# TH4.net
KiCad netlist of a schematic drawn in Altium Designer
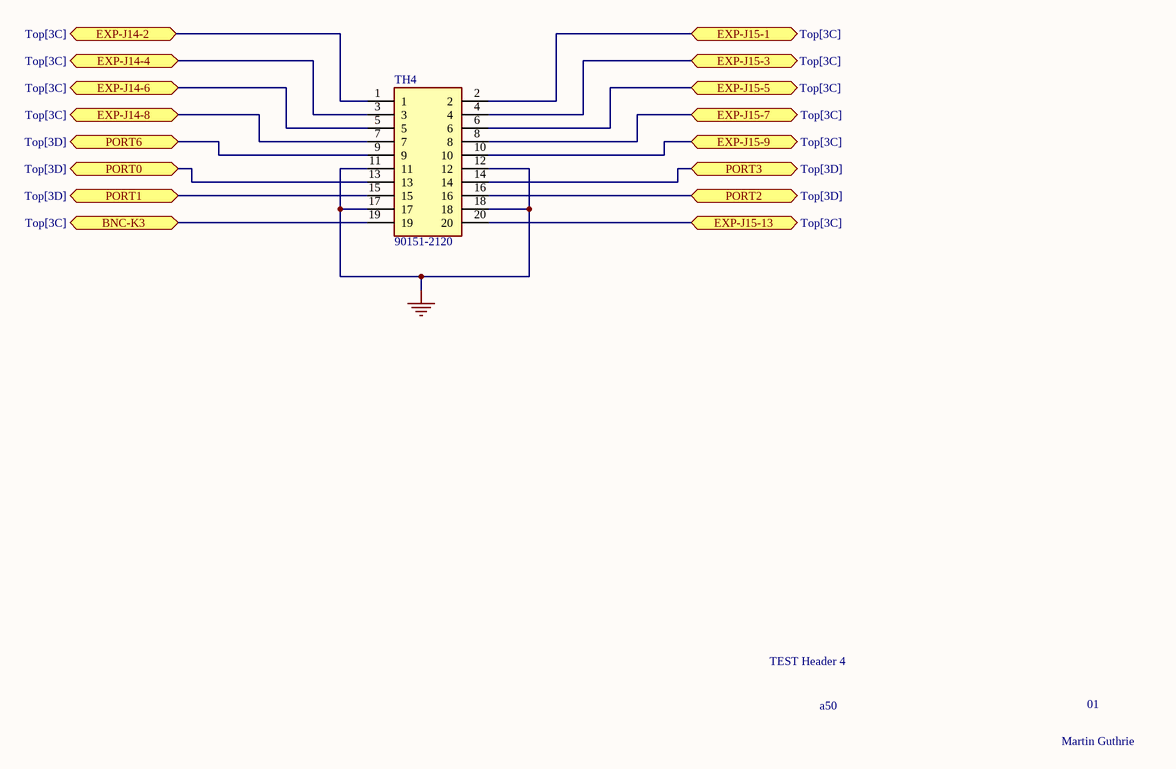
[diagram p0: TH4.SchDoc]

(export (version "E")
  (design (tool "Eeschema 10.0.6"))
  (components
    (comp (ref "TH4")
      (value "90151-2120")
      (footprint "PcbLib:90151-2120")
      (description "Connector")
      (fields (field (name "MOUSER PART NUMBER") "538-90151-2120"))
      (libsource (lib "SchematicLib") (part "90151-2120"))
    )
  )
  (nets
    (net (code "1") (name "/BNC-K3") (class "Default")
      (node (ref "TH4") (pin "19") (pinfunction "19_19") (pintype "passive"))
    )
    (net (code "2") (name "/EXP-J14-2") (class "Default")
      (node (ref "TH4") (pin "1") (pinfunction "1_1") (pintype "passive"))
    )
    (net (code "3") (name "/EXP-J14-4") (class "Default")
      (node (ref "TH4") (pin "3") (pinfunction "3_3") (pintype "passive"))
    )
    (net (code "4") (name "/EXP-J14-6") (class "Default")
      (node (ref "TH4") (pin "5") (pinfunction "5_5") (pintype "passive"))
    )
    (net (code "5") (name "/EXP-J14-8") (class "Default")
      (node (ref "TH4") (pin "7") (pinfunction "7_7") (pintype "passive"))
    )
    (net (code "6") (name "/EXP-J15-1") (class "Default")
      (node (ref "TH4") (pin "2") (pinfunction "2_2") (pintype "passive"))
    )
    (net (code "7") (name "/EXP-J15-3") (class "Default")
      (node (ref "TH4") (pin "4") (pinfunction "4_4") (pintype "passive"))
    )
    (net (code "8") (name "/EXP-J15-5") (class "Default")
      (node (ref "TH4") (pin "6") (pinfunction "6_6") (pintype "passive"))
    )
    (net (code "9") (name "/EXP-J15-7") (class "Default")
      (node (ref "TH4") (pin "8") (pinfunction "8_8") (pintype "passive"))
    )
    (net (code "10") (name "/EXP-J15-9") (class "Default")
      (node (ref "TH4") (pin "10") (pinfunction "10_10") (pintype "passive"))
    )
    (net (code "11") (name "/EXP-J15-13") (class "Default")
      (node (ref "TH4") (pin "20") (pinfunction "20_20") (pintype "passive"))
    )
    (net (code "12") (name "/PORT0") (class "Default")
      (node (ref "TH4") (pin "13") (pinfunction "13_13") (pintype "passive"))
    )
    (net (code "13") (name "/PORT1") (class "Default")
      (node (ref "TH4") (pin "15") (pinfunction "15_15") (pintype "passive"))
    )
    (net (code "14") (name "/PORT2") (class "Default")
      (node (ref "TH4") (pin "16") (pinfunction "16_16") (pintype "passive"))
    )
    (net (code "15") (name "/PORT3") (class "Default")
      (node (ref "TH4") (pin "14") (pinfunction "14_14") (pintype "passive"))
    )
    (net (code "16") (name "/PORT6") (class "Default")
      (node (ref "TH4") (pin "9") (pinfunction "9_9") (pintype "passive"))
    )
    (net (code "17") (name "GND") (class "Default")
      (node (ref "TH4") (pin "11") (pinfunction "11_11") (pintype "passive"))
      (node (ref "TH4") (pin "12") (pinfunction "12_12") (pintype "passive"))
      (node (ref "TH4") (pin "17") (pinfunction "17_17") (pintype "passive"))
      (node (ref "TH4") (pin "18") (pinfunction "18_18") (pintype "passive"))
    )
  )
)
